# OpenROV_Light_Board_2_7A.net
KiCad netlist of a schematic drawn in EAGLE
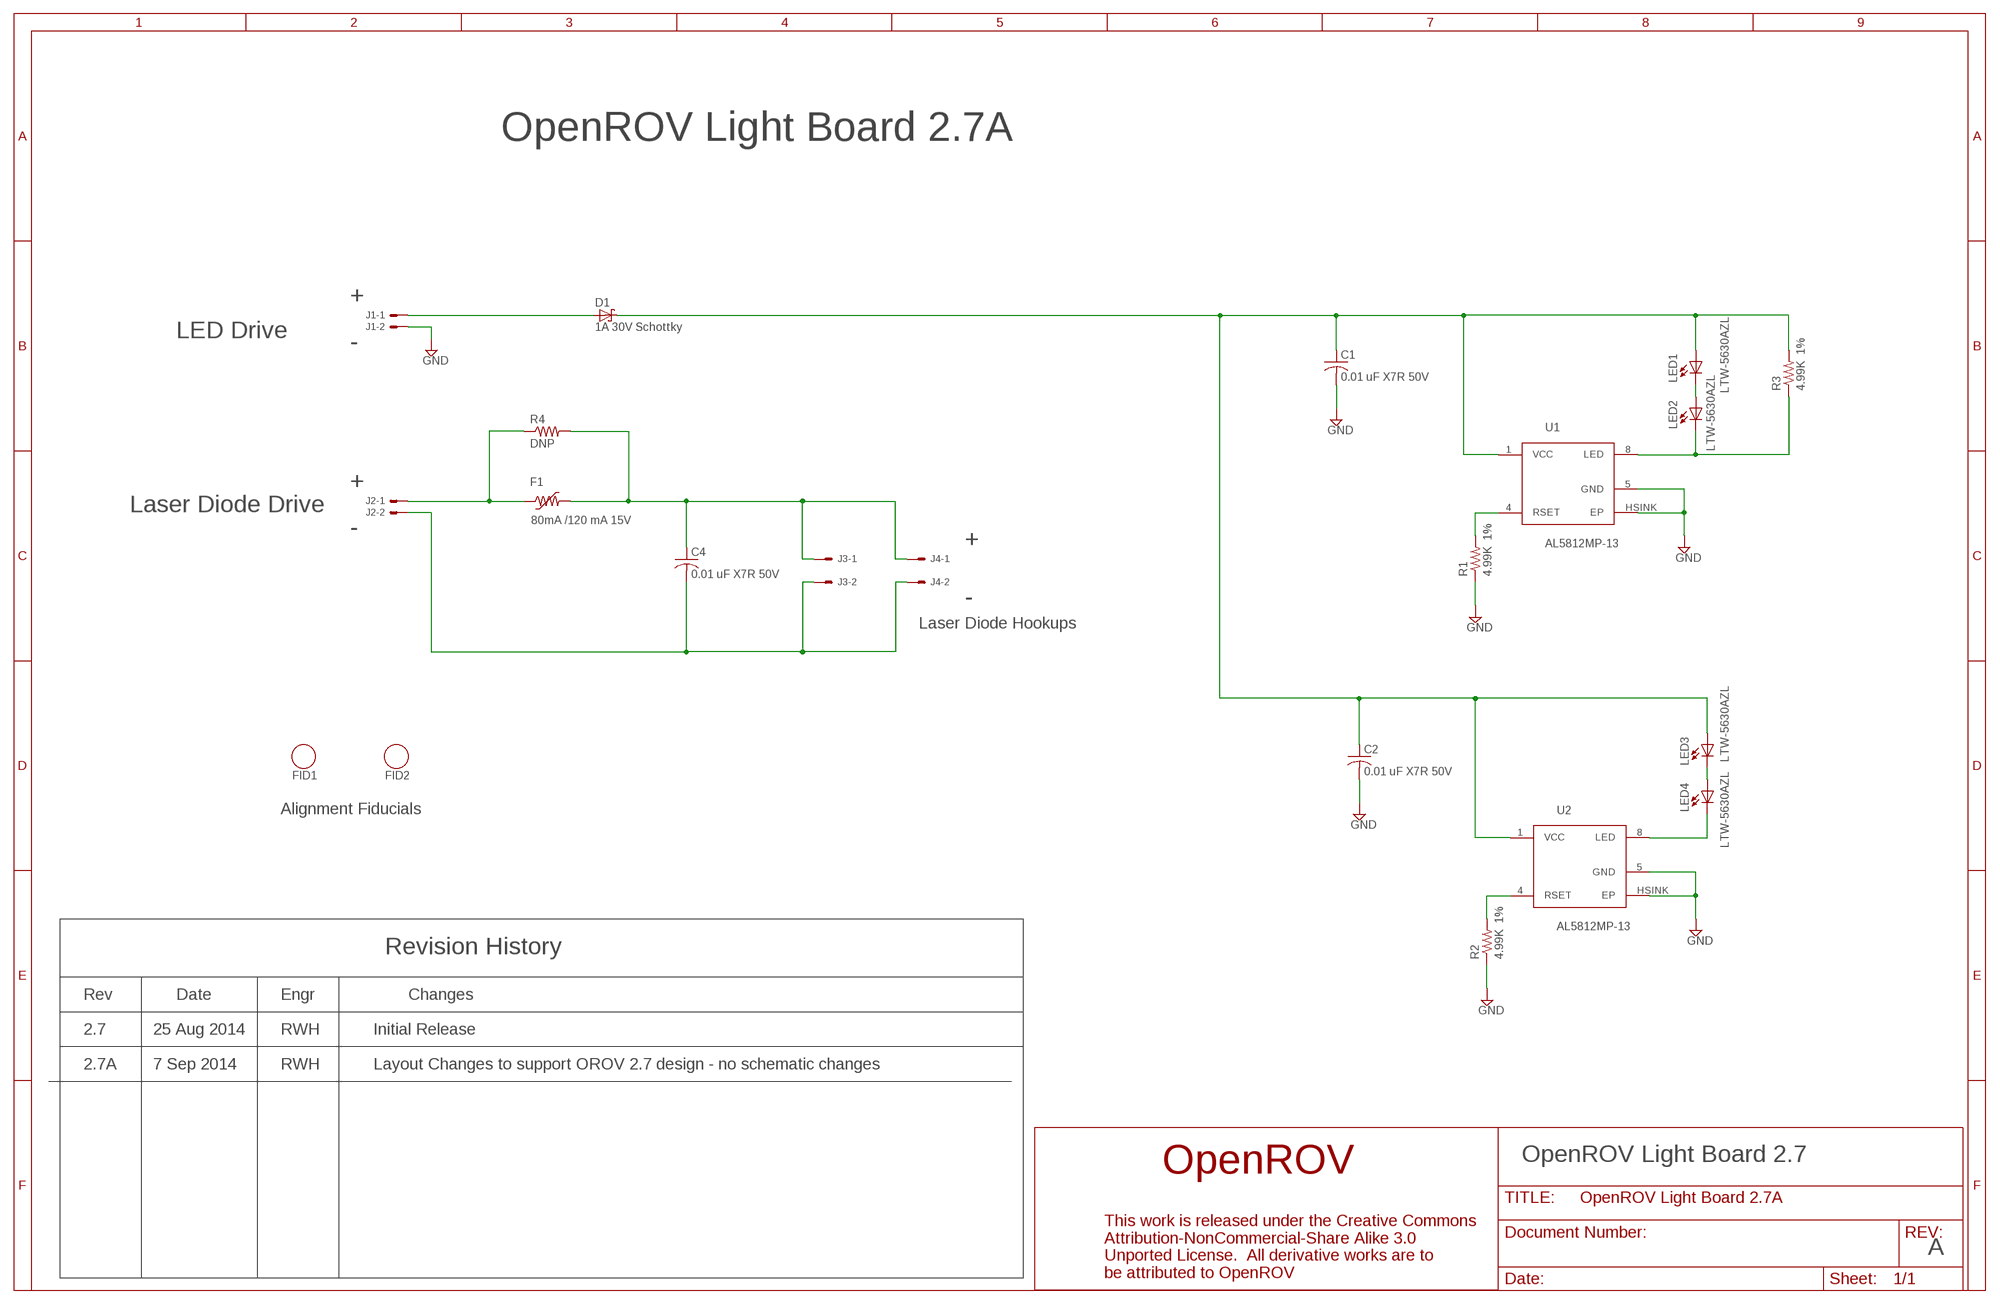
[diagram p0: schematic, sheet 1]

(export (version "E")
  (design (tool "Eeschema 10.0.6"))
  (components
    (comp (ref "C1")
      (value "0.01 uF X7R 50V")
      (footprint "eagle-import:R0603")
      (libsource (lib "eagle-import") (part "CAP0603"))
    )
    (comp (ref "C2")
      (value "0.01 uF X7R 50V")
      (footprint "eagle-import:R0603")
      (libsource (lib "eagle-import") (part "CAP0603"))
    )
    (comp (ref "C4")
      (value "0.01 uF X7R 50V")
      (footprint "eagle-import:R0603")
      (libsource (lib "eagle-import") (part "CAP0603"))
    )
    (comp (ref "D1")
      (value "1A 30V Schottky")
      (footprint "eagle-import:DO214AC")
      (libsource (lib "eagle-import") (part "SCHOTTKYDO214AC"))
    )
    (comp (ref "F1")
      (value "80mA /120 mA 15V")
      (footprint "eagle-import:R0603")
      (libsource (lib "eagle-import") (part "POLYFUSE-0603"))
    )
    (comp (ref "FID1")
      (value "FIDUCIAL_1")
      (footprint "eagle-import:FIDUCIAL_1")
      (libsource (lib "eagle-import") (part "FIDUCIAL_1"))
    )
    (comp (ref "FID2")
      (value "FIDUCIAL_1")
      (footprint "eagle-import:FIDUCIAL_1")
      (libsource (lib "eagle-import") (part "FIDUCIAL_1"))
    )
    (comp (ref "J1")
      (value "HDR_1X2X0.100-ALT_SILK")
      (footprint "eagle-import:22-23-2021_ALT_SILK")
      (libsource (lib "eagle-import") (part "HDR_1X2X0.100-ALT_SILK"))
    )
    (comp (ref "J2")
      (value "HDR_1X2X0.100-ALT_SILK")
      (footprint "eagle-import:22-23-2021_ALT_SILK")
      (libsource (lib "eagle-import") (part "HDR_1X2X0.100-ALT_SILK"))
    )
    (comp (ref "J3")
      (value "HDR_1X2X2MM")
      (footprint "eagle-import:87758-0216")
      (fields (field (name "MPN") "87758-0216"))
      (libsource (lib "eagle-import") (part "HDR_1X2X2MM"))
    )
    (comp (ref "J4")
      (value "HDR_1X2X2MM")
      (footprint "eagle-import:87758-0216")
      (fields (field (name "MPN") "87758-0216"))
      (libsource (lib "eagle-import") (part "HDR_1X2X2MM"))
    )
    (comp (ref "LED1")
      (value "LTW-5630AZL")
      (footprint "eagle-import:LITEON-5630")
      (libsource (lib "eagle-import") (part "LTW-5630AZL"))
    )
    (comp (ref "LED2")
      (value "LTW-5630AZL")
      (footprint "eagle-import:LITEON-5630")
      (libsource (lib "eagle-import") (part "LTW-5630AZL"))
    )
    (comp (ref "LED3")
      (value "LTW-5630AZL")
      (footprint "eagle-import:LITEON-5630")
      (libsource (lib "eagle-import") (part "LTW-5630AZL"))
    )
    (comp (ref "LED4")
      (value "LTW-5630AZL")
      (footprint "eagle-import:LITEON-5630")
      (libsource (lib "eagle-import") (part "LTW-5630AZL"))
    )
    (comp (ref "R1")
      (value "4.99K 1%")
      (footprint "eagle-import:R0603")
      (libsource (lib "eagle-import") (part "RESISTOR-0603"))
    )
    (comp (ref "R2")
      (value "4.99K 1%")
      (footprint "eagle-import:R0603")
      (libsource (lib "eagle-import") (part "RESISTOR-0603"))
    )
    (comp (ref "R3")
      (value "4.99K 1%")
      (footprint "eagle-import:R0603")
      (libsource (lib "eagle-import") (part "RESISTOR-0603"))
    )
    (comp (ref "R4")
      (value "DNP")
      (footprint "eagle-import:R1206")
      (libsource (lib "eagle-import") (part "RESISTOR-1206"))
    )
    (comp (ref "U1")
      (value "AL5812MP-13")
      (footprint "eagle-import:MSOP-8EP")
      (libsource (lib "eagle-import") (part "AL5812MP-13"))
    )
    (comp (ref "U2")
      (value "AL5812MP-13")
      (footprint "eagle-import:MSOP-8EP")
      (libsource (lib "eagle-import") (part "AL5812MP-13"))
    )
  )
  (nets
    (net (code "1") (name "GND") (class "Default")
      (node (ref "C1") (pin "2") (pinfunction "2_2") (pintype "passive"))
      (node (ref "C2") (pin "2") (pinfunction "2_2") (pintype "passive"))
      (node (ref "J1") (pin "2") (pinfunction "S_2") (pintype "passive"))
      (node (ref "R1") (pin "1") (pinfunction "1_1") (pintype "passive"))
      (node (ref "R2") (pin "1") (pinfunction "1_1") (pintype "passive"))
      (node (ref "U1") (pin "5") (pinfunction "GND_5") (pintype "bidirectional"))
      (node (ref "U1") (pin "HSINK") (pinfunction "EP_HSINK") (pintype "bidirectional"))
      (node (ref "U2") (pin "5") (pinfunction "GND_5") (pintype "bidirectional"))
      (node (ref "U2") (pin "HSINK") (pinfunction "EP_HSINK") (pintype "bidirectional"))
    )
    (net (code "2") (name "Net-(J1A-S)") (class "Default")
      (node (ref "D1") (pin "A") (pinfunction "A_A") (pintype "passive"))
      (node (ref "J1") (pin "1") (pinfunction "S_1") (pintype "passive"))
    )
    (net (code "3") (name "Net-(J2A-S)") (class "Default")
      (node (ref "F1") (pin "1") (pinfunction "1_1") (pintype "passive"))
      (node (ref "J2") (pin "1") (pinfunction "S_1") (pintype "passive"))
      (node (ref "R4") (pin "1") (pinfunction "1_1") (pintype "passive"))
    )
    (net (code "4") (name "Net-(J2B-S)") (class "Default")
      (node (ref "C4") (pin "2") (pinfunction "2_2") (pintype "passive"))
      (node (ref "J2") (pin "2") (pinfunction "S_2") (pintype "passive"))
      (node (ref "J3") (pin "2") (pinfunction "S_2") (pintype "passive"))
      (node (ref "J4") (pin "2") (pinfunction "S_2") (pintype "passive"))
    )
    (net (code "5") (name "Net-(J3A-S)") (class "Default")
      (node (ref "C4") (pin "1") (pinfunction "1_1") (pintype "passive"))
      (node (ref "F1") (pin "2") (pinfunction "2_2") (pintype "passive"))
      (node (ref "J3") (pin "1") (pinfunction "S_1") (pintype "passive"))
      (node (ref "J4") (pin "1") (pinfunction "S_1") (pintype "passive"))
      (node (ref "R4") (pin "2") (pinfunction "2_2") (pintype "passive"))
    )
    (net (code "6") (name "Net-(LED1-C-PadC1)") (class "Default")
      (node (ref "LED1") (pin "C1") (pinfunction "C_C1") (pintype "passive"))
      (node (ref "LED1") (pin "C2") (pinfunction "C_C2") (pintype "passive"))
      (node (ref "LED2") (pin "A1") (pinfunction "A_A1") (pintype "passive"))
      (node (ref "LED2") (pin "A2") (pinfunction "A_A2") (pintype "passive"))
      (node (ref "LED2") (pin "A3") (pinfunction "A_A3") (pintype "passive"))
    )
    (net (code "7") (name "Net-(LED3-C-PadC1)") (class "Default")
      (node (ref "LED3") (pin "C1") (pinfunction "C_C1") (pintype "passive"))
      (node (ref "LED3") (pin "C2") (pinfunction "C_C2") (pintype "passive"))
      (node (ref "LED4") (pin "A1") (pinfunction "A_A1") (pintype "passive"))
      (node (ref "LED4") (pin "A2") (pinfunction "A_A2") (pintype "passive"))
      (node (ref "LED4") (pin "A3") (pinfunction "A_A3") (pintype "passive"))
    )
    (net (code "8") (name "Net-(U1-LED)") (class "Default")
      (node (ref "LED2") (pin "C1") (pinfunction "C_C1") (pintype "passive"))
      (node (ref "LED2") (pin "C2") (pinfunction "C_C2") (pintype "passive"))
      (node (ref "R3") (pin "1") (pinfunction "1_1") (pintype "passive"))
      (node (ref "U1") (pin "8") (pinfunction "LED_8") (pintype "bidirectional"))
    )
    (net (code "9") (name "Net-(U1-RSET)") (class "Default")
      (node (ref "R1") (pin "2") (pinfunction "2_2") (pintype "passive"))
      (node (ref "U1") (pin "4") (pinfunction "RSET_4") (pintype "bidirectional"))
    )
    (net (code "10") (name "Net-(U1-VCC)") (class "Default")
      (node (ref "C1") (pin "1") (pinfunction "1_1") (pintype "passive"))
      (node (ref "C2") (pin "1") (pinfunction "1_1") (pintype "passive"))
      (node (ref "D1") (pin "C") (pinfunction "C_C") (pintype "passive"))
      (node (ref "LED1") (pin "A1") (pinfunction "A_A1") (pintype "passive"))
      (node (ref "LED1") (pin "A2") (pinfunction "A_A2") (pintype "passive"))
      (node (ref "LED1") (pin "A3") (pinfunction "A_A3") (pintype "passive"))
      (node (ref "LED3") (pin "A1") (pinfunction "A_A1") (pintype "passive"))
      (node (ref "LED3") (pin "A2") (pinfunction "A_A2") (pintype "passive"))
      (node (ref "LED3") (pin "A3") (pinfunction "A_A3") (pintype "passive"))
      (node (ref "R3") (pin "2") (pinfunction "2_2") (pintype "passive"))
      (node (ref "U1") (pin "1") (pinfunction "VCC_1") (pintype "bidirectional"))
      (node (ref "U2") (pin "1") (pinfunction "VCC_1") (pintype "bidirectional"))
    )
    (net (code "11") (name "Net-(U2-LED)") (class "Default")
      (node (ref "LED4") (pin "C1") (pinfunction "C_C1") (pintype "passive"))
      (node (ref "LED4") (pin "C2") (pinfunction "C_C2") (pintype "passive"))
      (node (ref "U2") (pin "8") (pinfunction "LED_8") (pintype "bidirectional"))
    )
    (net (code "12") (name "Net-(U2-RSET)") (class "Default")
      (node (ref "R2") (pin "2") (pinfunction "2_2") (pintype "passive"))
      (node (ref "U2") (pin "4") (pinfunction "RSET_4") (pintype "bidirectional"))
    )
  )
)
